# SOLoRa.net
KiCad netlist of a schematic drawn in EAGLE
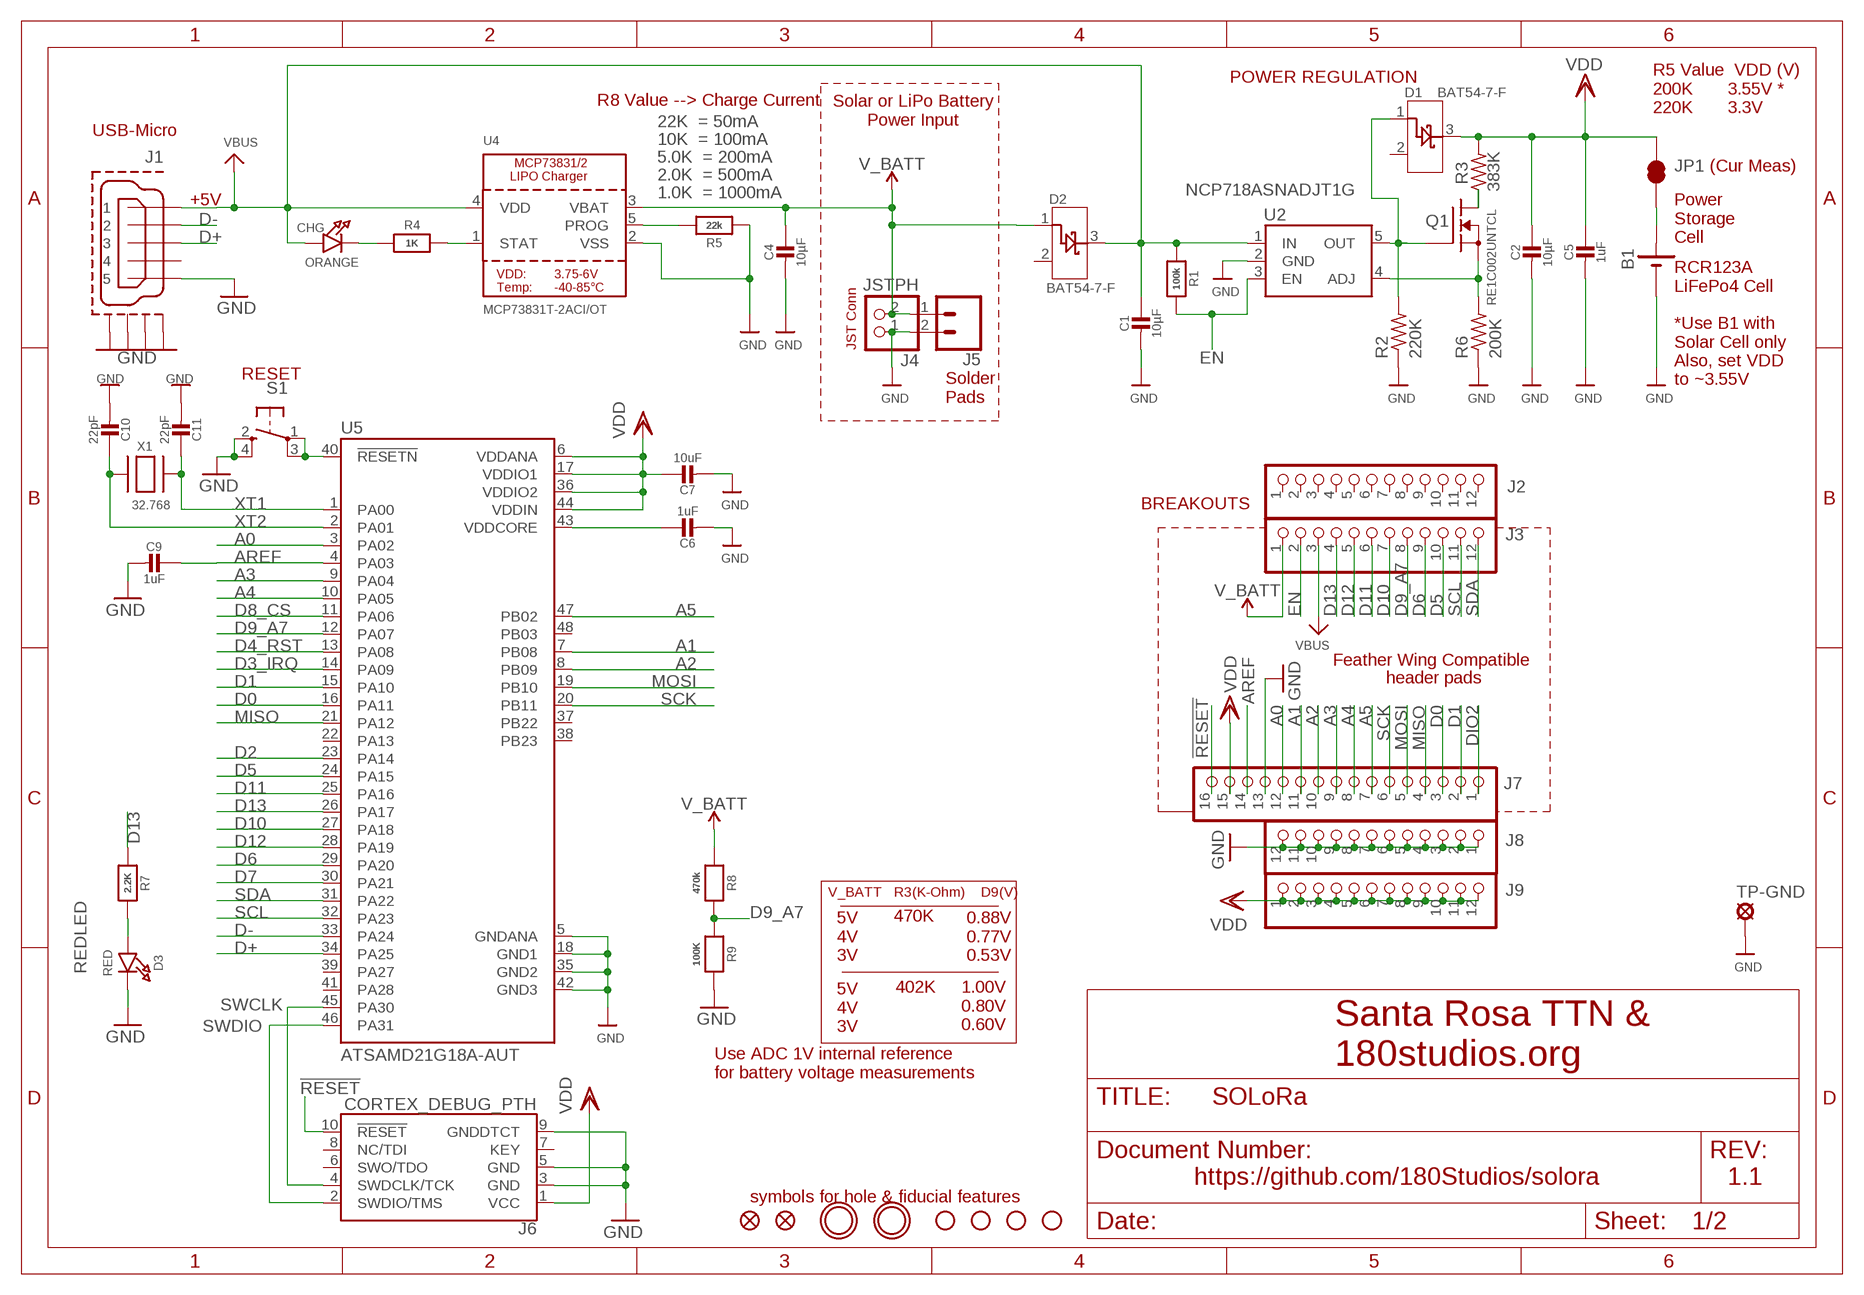
[diagram p0: schematic, sheet 1]
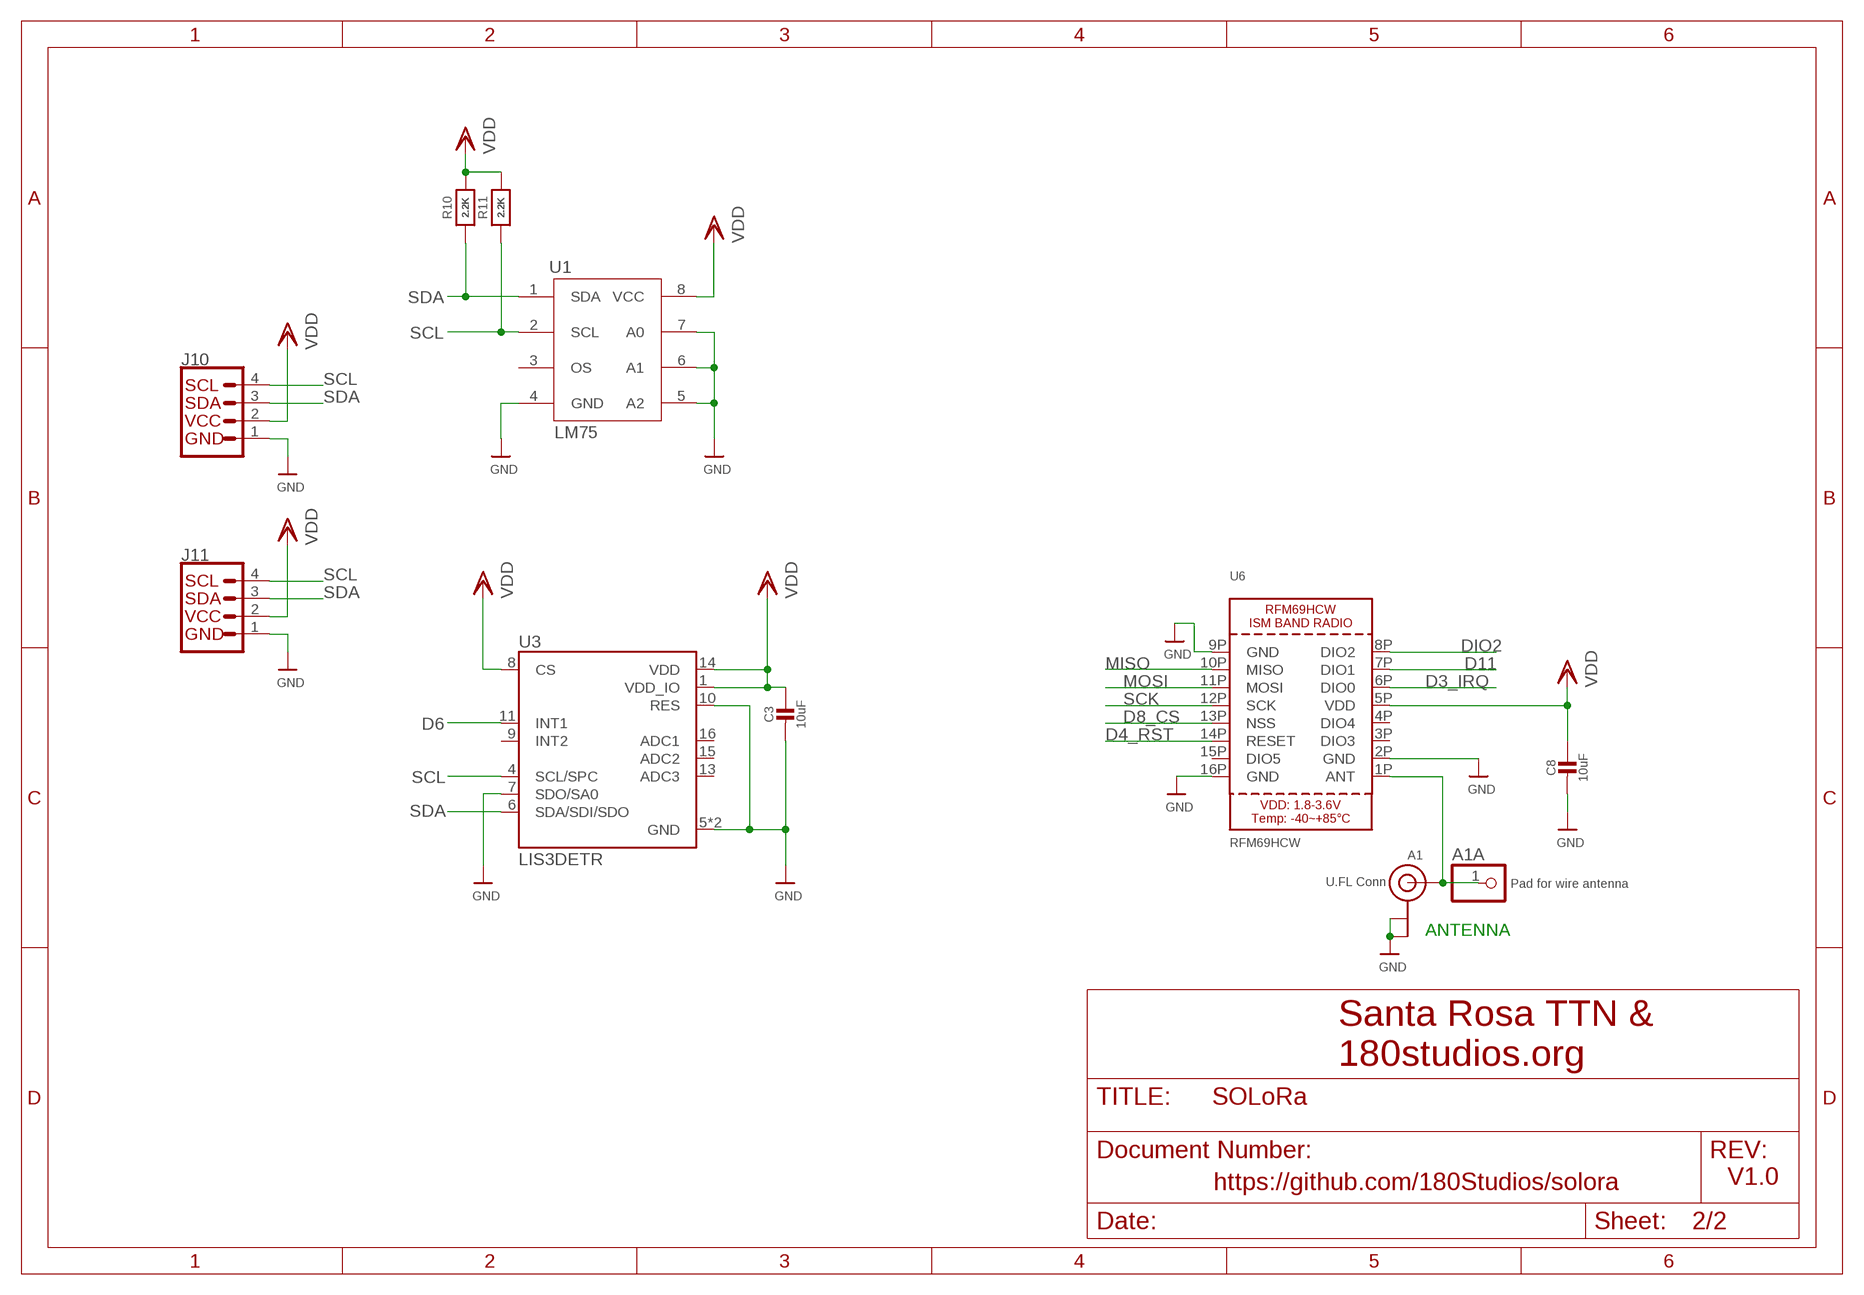
[diagram p1: schematic, sheet 2]

(export (version "E")
  (design (tool "Eeschema 10.0.6"))
  (components
    (comp (ref "$$U$1")
      (value "FIDUCIAL\"\"")
      (footprint "eagle-import:FIDUCIAL_1MM")
      (libsource (lib "eagle-import") (part "FIDUCIAL{dblquote}{dblquote}"))
    )
    (comp (ref "$$U$2")
      (value "MOUNTINGHOLE2.5")
      (footprint "eagle-import:MOUNTINGHOLE_2.5_PLATED")
      (libsource (lib "eagle-import") (part "MOUNTINGHOLE2.5"))
    )
    (comp (ref "$$U$3")
      (value "MOUNTINGHOLE2.5")
      (footprint "eagle-import:MOUNTINGHOLE_2.5_PLATED")
      (libsource (lib "eagle-import") (part "MOUNTINGHOLE2.5"))
    )
    (comp (ref "$$U$4")
      (value "FIDUCIAL\"\"")
      (footprint "eagle-import:FIDUCIAL_1MM")
      (libsource (lib "eagle-import") (part "FIDUCIAL{dblquote}{dblquote}"))
    )
    (comp (ref "B1")
      (value "BH123A")
      (footprint "eagle-import:BH123A")
      (libsource (lib "eagle-import") (part "BH123A"))
    )
    (comp (ref "C1")
      (value "10µF")
      (footprint "eagle-import:0805-NO")
      (libsource (lib "eagle-import") (part "CAP_CERAMIC0805-NOOUTLINE"))
    )
    (comp (ref "C2")
      (value "10µF")
      (footprint "eagle-import:0805-NO")
      (libsource (lib "eagle-import") (part "CAP_CERAMIC0805-NOOUTLINE"))
    )
    (comp (ref "C4")
      (value "10µF")
      (footprint "eagle-import:0805-NO")
      (libsource (lib "eagle-import") (part "CAP_CERAMIC0805-NOOUTLINE"))
    )
    (comp (ref "C5")
      (value "1uF")
      (footprint "eagle-import:0603-NO")
      (libsource (lib "eagle-import") (part "CAP_CERAMIC0603_NO"))
    )
    (comp (ref "C6")
      (value "1uF")
      (footprint "eagle-import:0603-NO")
      (libsource (lib "eagle-import") (part "CAP_CERAMIC0603_NO"))
    )
    (comp (ref "C7")
      (value "10uF")
      (footprint "eagle-import:0805-NO")
      (libsource (lib "eagle-import") (part "CAP_CERAMIC0805-NOOUTLINE"))
    )
    (comp (ref "C9")
      (value "1uF")
      (footprint "eagle-import:0603-NO")
      (libsource (lib "eagle-import") (part "CAP_CERAMIC0603_NO"))
    )
    (comp (ref "C10")
      (value "22pF")
      (footprint "eagle-import:0603-NO")
      (libsource (lib "eagle-import") (part "CAP_CERAMIC0603_NO"))
    )
    (comp (ref "C11")
      (value "22pF")
      (footprint "eagle-import:0603-NO")
      (libsource (lib "eagle-import") (part "CAP_CERAMIC0603_NO"))
    )
    (comp (ref "CHG")
      (value "ORANGE")
      (footprint "eagle-import:CHIPLED_0805_NOOUTLINE")
      (libsource (lib "eagle-import") (part "LED0805_NOOUTLINE"))
    )
    (comp (ref "D1")
      (value "BAT54-7-F")
      (footprint "eagle-import:SOT-23")
      (fields (field (name "MANUFACTURER_PART_NUMBER") "BAT547F"))
      (libsource (lib "eagle-import") (part "BAT54-7-F"))
    )
    (comp (ref "D2")
      (value "BAT54-7-F")
      (footprint "eagle-import:SOT-23")
      (fields (field (name "MANUFACTURER_PART_NUMBER") "BAT547F"))
      (libsource (lib "eagle-import") (part "BAT54-7-F"))
    )
    (comp (ref "D3")
      (value "RED")
      (footprint "eagle-import:CHIPLED_0805_NOOUTLINE")
      (libsource (lib "eagle-import") (part "LED0805_NOOUTLINE"))
    )
    (comp (ref "H1")
      (value "STAND-OFF")
      (footprint "eagle-import:STAND-OFF")
      (libsource (lib "eagle-import") (part "STAND-OFF"))
    )
    (comp (ref "H2")
      (value "STAND-OFF")
      (footprint "eagle-import:STAND-OFF")
      (libsource (lib "eagle-import") (part "STAND-OFF"))
    )
    (comp (ref "H3")
      (value "STAND-OFF")
      (footprint "eagle-import:STAND-OFF")
      (libsource (lib "eagle-import") (part "STAND-OFF"))
    )
    (comp (ref "H4")
      (value "STAND-OFF")
      (footprint "eagle-import:STAND-OFF")
      (libsource (lib "eagle-import") (part "STAND-OFF"))
    )
    (comp (ref "J1")
      (value "CONN_USB-MIRCO_10118194")
      (footprint "eagle-import:10118194_USB")
      (libsource (lib "eagle-import") (part "CONN_USB-MIRCO_10118194"))
    )
    (comp (ref "J2")
      (value "HEADER-1X12")
      (footprint "eagle-import:1X12_ROUND")
      (libsource (lib "eagle-import") (part "HEADER-1X12"))
    )
    (comp (ref "J3")
      (value "HEADER-1X12")
      (footprint "eagle-import:1X12_ROUND")
      (libsource (lib "eagle-import") (part "HEADER-1X12"))
    )
    (comp (ref "J4")
      (value "JSTPH")
      (footprint "eagle-import:JSTPH2")
      (libsource (lib "eagle-import") (part "CON_JST_PH_2PIN"))
    )
    (comp (ref "J5")
      (value "CONN_021X02_NO_SILK")
      (footprint "eagle-import:1X02_NO_SILK")
      (libsource (lib "eagle-import") (part "CONN_021X02_NO_SILK"))
    )
    (comp (ref "J6")
      (value "CORTEX_DEBUG_PTH")
      (footprint "eagle-import:2X5-PTH-1.27MM")
      (libsource (lib "eagle-import") (part "CORTEX_DEBUG_PTH"))
    )
    (comp (ref "J7")
      (value "HEADER-1X16ROUND")
      (footprint "eagle-import:1X16_ROUND")
      (libsource (lib "eagle-import") (part "HEADER-1X16ROUND"))
    )
    (comp (ref "J8")
      (value "HEADER-1X12")
      (footprint "eagle-import:1X12_ROUND")
      (libsource (lib "eagle-import") (part "HEADER-1X12"))
    )
    (comp (ref "J9")
      (value "HEADER-1X12")
      (footprint "eagle-import:1X12_ROUND")
      (libsource (lib "eagle-import") (part "HEADER-1X12"))
    )
    (comp (ref "JP1")
      (value "JUMPER-SMT_2_NC_TRACE_NO-SILK")
      (footprint "eagle-import:SMT-JUMPER_2_NC_TRACE_NO-SILK")
      (libsource (lib "eagle-import") (part "JUMPER-SMT_2_NC_TRACE_NO-SILK"))
    )
    (comp (ref "Q1")
      (value "RE1C002UNTCL")
      (footprint "eagle-import:SOT50P160X85-3N")
      (fields (field (name "RS_PART_NUMBER") "1246784P"))
      (libsource (lib "eagle-import") (part "RE1C002UNTCL"))
    )
    (comp (ref "R1")
      (value "100k")
      (footprint "eagle-import:0603-NO")
      (libsource (lib "eagle-import") (part "RESISTOR_0603_NOOUT"))
    )
    (comp (ref "R2")
      (value "220K")
      (footprint "eagle-import:R0603")
      (libsource (lib "eagle-import") (part "R-US_R0603"))
    )
    (comp (ref "R3")
      (value "383K")
      (footprint "eagle-import:R0603")
      (libsource (lib "eagle-import") (part "R-US_R0603"))
    )
    (comp (ref "R4")
      (value "1K")
      (footprint "eagle-import:0603-NO")
      (libsource (lib "eagle-import") (part "RESISTOR_0603_NOOUT"))
    )
    (comp (ref "R5")
      (value "22k")
      (footprint "eagle-import:0603-NO")
      (libsource (lib "eagle-import") (part "RESISTOR_0603_NOOUT"))
    )
    (comp (ref "R6")
      (value "200K")
      (footprint "eagle-import:R0603")
      (libsource (lib "eagle-import") (part "R-US_R0603"))
    )
    (comp (ref "R7")
      (value "2.2K")
      (footprint "eagle-import:0603-NO")
      (libsource (lib "eagle-import") (part "RESISTOR_0603_NOOUT"))
    )
    (comp (ref "R8")
      (value "470k")
      (footprint "eagle-import:0603-NO")
      (libsource (lib "eagle-import") (part "RESISTOR_0603_NOOUT"))
    )
    (comp (ref "R9")
      (value "100K")
      (footprint "eagle-import:0603-NO")
      (libsource (lib "eagle-import") (part "RESISTOR_0603_NOOUT"))
    )
    (comp (ref "S1")
      (value "SPST_TACT-KMR2")
      (footprint "eagle-import:KMR2")
      (libsource (lib "eagle-import") (part "SPST_TACT-KMR2"))
    )
    (comp (ref "TP-GND")
      (value "SE14")
      (footprint "eagle-import:SE14")
      (libsource (lib "eagle-import") (part "SE14"))
    )
    (comp (ref "U2")
      (value "NCP718ASNADJT1G")
      (footprint "eagle-import:SOT95P280X100-5N")
      (fields (field (name "RS_PART_NUMBER") "1723327"))
      (libsource (lib "eagle-import") (part "NCP718ASNADJT1G"))
    )
    (comp (ref "U4")
      (value "MCP73831T-2ACI/OT")
      (footprint "eagle-import:SOT23-5")
      (libsource (lib "eagle-import") (part "MCP73831/2"))
    )
    (comp (ref "U5")
      (value "ATSAMD21G18A-AUT")
      (footprint "eagle-import:QFP50P900X900X120-48N")
      (fields (field (name "DIGI-KEY_PART_NUMBER") "ATSAMD21G18A-AUTCT-ND") (field (name "MF") "Microchip"))
      (libsource (lib "eagle-import") (part "ATSAMD21G18A-AUT"))
    )
    (comp (ref "X1")
      (value "32.768")
      (footprint "eagle-import:XTAL3215")
      (libsource (lib "eagle-import") (part "XTAL-3.2X1.5"))
    )
    (comp (ref "A1")
      (value "U.FL Conn")
      (footprint "eagle-import:U.FL")
      (libsource (lib "eagle-import") (part "ANTENNA_U.FL"))
    )
    (comp (ref "A1A")
      (value "Pad for wire antenna")
      (footprint "eagle-import:1X01_ROUND")
      (libsource (lib "eagle-import") (part "HEADER-1X1ROUND"))
    )
    (comp (ref "C3")
      (value "10uF")
      (footprint "eagle-import:0805-NO")
      (libsource (lib "eagle-import") (part "CAP_CERAMIC0805-NOOUTLINE"))
    )
    (comp (ref "C8")
      (value "10uF")
      (footprint "eagle-import:0805-NO")
      (libsource (lib "eagle-import") (part "CAP_CERAMIC0805-NOOUTLINE"))
    )
    (comp (ref "J10")
      (value "QWIIC_CONNECTORJS-1MM")
      (footprint "eagle-import:1X04_1MM_RA")
      (libsource (lib "eagle-import") (part "QWIIC_CONNECTORJS-1MM"))
    )
    (comp (ref "J11")
      (value "QWIIC_CONNECTORJS-1MM")
      (footprint "eagle-import:1X04_1MM_RA")
      (libsource (lib "eagle-import") (part "QWIIC_CONNECTORJS-1MM"))
    )
    (comp (ref "R10")
      (value "2.2K")
      (footprint "eagle-import:0603-NO")
      (libsource (lib "eagle-import") (part "RESISTOR_0603_NOOUT"))
    )
    (comp (ref "R11")
      (value "2.2K")
      (footprint "eagle-import:0603-NO")
      (libsource (lib "eagle-import") (part "RESISTOR_0603_NOOUT"))
    )
    (comp (ref "U1")
      (value "LM75")
      (footprint "eagle-import:SO8")
      (libsource (lib "eagle-import") (part "LM75"))
    )
    (comp (ref "U3")
      (value "LIS3DETR")
      (footprint "eagle-import:LGA16R50P5X3_300X300X100N")
      (fields (field (name "DIGI-KEY_PART_NUMBER") "497-16262-1-ND") (field (name "MF") "STMicroelectronics"))
      (libsource (lib "eagle-import") (part "LIS3DETR"))
    )
    (comp (ref "U6")
      (value "RFM69HCW")
      (footprint "eagle-import:RFMHCW_SMT")
      (libsource (lib "eagle-import") (part "RFM69HCW_SMT"))
    )
  )
  (nets
    (net (code "1") (name "A0") (class "Default")
      (node (ref "J7") (pin "12") (pinfunction "12_12") (pintype "passive"))
      (node (ref "U5") (pin "3") (pinfunction "PA02_3") (pintype "bidirectional"))
    )
    (net (code "2") (name "A1") (class "Default")
      (node (ref "J7") (pin "11") (pinfunction "11_11") (pintype "passive"))
      (node (ref "U5") (pin "7") (pinfunction "PB08_7") (pintype "bidirectional"))
    )
    (net (code "3") (name "A2") (class "Default")
      (node (ref "J7") (pin "10") (pinfunction "10_10") (pintype "passive"))
      (node (ref "U5") (pin "8") (pinfunction "PB09_8") (pintype "bidirectional"))
    )
    (net (code "4") (name "A3") (class "Default")
      (node (ref "J7") (pin "9") (pinfunction "9_9") (pintype "passive"))
      (node (ref "U5") (pin "9") (pinfunction "PA04_9") (pintype "bidirectional"))
    )
    (net (code "5") (name "A4") (class "Default")
      (node (ref "J7") (pin "8") (pinfunction "8_8") (pintype "passive"))
      (node (ref "U5") (pin "10") (pinfunction "PA05_10") (pintype "bidirectional"))
    )
    (net (code "6") (name "A5") (class "Default")
      (node (ref "J7") (pin "7") (pinfunction "7_7") (pintype "passive"))
      (node (ref "U5") (pin "47") (pinfunction "PB02_47") (pintype "bidirectional"))
    )
    (net (code "7") (name "AREF") (class "Default")
      (node (ref "C9") (pin "1") (pinfunction "1_1") (pintype "passive"))
      (node (ref "J7") (pin "14") (pinfunction "14_14") (pintype "passive"))
      (node (ref "U5") (pin "4") (pinfunction "PA03_4") (pintype "bidirectional"))
    )
    (net (code "8") (name "D+") (class "Default")
      (node (ref "J1") (pin "3") (pinfunction "3_3") (pintype "input"))
      (node (ref "U5") (pin "34") (pinfunction "PA25_34") (pintype "bidirectional"))
    )
    (net (code "9") (name "D-") (class "Default")
      (node (ref "J1") (pin "2") (pinfunction "2_2") (pintype "input"))
      (node (ref "U5") (pin "33") (pinfunction "PA24_33") (pintype "bidirectional"))
    )
    (net (code "10") (name "D0") (class "Default")
      (node (ref "J7") (pin "3") (pinfunction "3_3") (pintype "passive"))
      (node (ref "U5") (pin "16") (pinfunction "PA11_16") (pintype "bidirectional"))
    )
    (net (code "11") (name "D1") (class "Default")
      (node (ref "J7") (pin "2") (pinfunction "2_2") (pintype "passive"))
      (node (ref "U5") (pin "15") (pinfunction "PA10_15") (pintype "bidirectional"))
    )
    (net (code "12") (name "D2") (class "Default")
      (node (ref "U5") (pin "23") (pinfunction "PA14_23") (pintype "bidirectional"))
    )
    (net (code "13") (name "D3_IRQ") (class "Default")
      (node (ref "U5") (pin "14") (pinfunction "PA09_14") (pintype "bidirectional"))
      (node (ref "U6") (pin "6P") (pinfunction "DIO0_6P") (pintype "bidirectional"))
    )
    (net (code "14") (name "D4_RST") (class "Default")
      (node (ref "U5") (pin "13") (pinfunction "PA08_13") (pintype "bidirectional"))
      (node (ref "U6") (pin "14P") (pinfunction "RESET_14P") (pintype "input"))
    )
    (net (code "15") (name "D5") (class "Default")
      (node (ref "J3") (pin "10") (pinfunction "10_10") (pintype "passive"))
      (node (ref "U5") (pin "24") (pinfunction "PA15_24") (pintype "bidirectional"))
    )
    (net (code "16") (name "D6") (class "Default")
      (node (ref "J3") (pin "9") (pinfunction "9_9") (pintype "passive"))
      (node (ref "U3") (pin "11") (pinfunction "INT1_11") (pintype "input"))
      (node (ref "U5") (pin "29") (pinfunction "PA20_29") (pintype "bidirectional"))
    )
    (net (code "17") (name "D7") (class "Default")
      (node (ref "U5") (pin "30") (pinfunction "PA21_30") (pintype "bidirectional"))
    )
    (net (code "18") (name "D8_CS") (class "Default")
      (node (ref "U5") (pin "11") (pinfunction "PA06_11") (pintype "bidirectional"))
      (node (ref "U6") (pin "13P") (pinfunction "NSS_13P") (pintype "input"))
    )
    (net (code "19") (name "D9_A7") (class "Default")
      (node (ref "J3") (pin "8") (pinfunction "8_8") (pintype "passive"))
      (node (ref "R8") (pin "2") (pinfunction "2_2") (pintype "passive"))
      (node (ref "R9") (pin "1") (pinfunction "1_1") (pintype "passive"))
      (node (ref "U5") (pin "12") (pinfunction "PA07_12") (pintype "bidirectional"))
    )
    (net (code "20") (name "D10") (class "Default")
      (node (ref "J3") (pin "7") (pinfunction "7_7") (pintype "passive"))
      (node (ref "U5") (pin "27") (pinfunction "PA18_27") (pintype "bidirectional"))
    )
    (net (code "21") (name "D11") (class "Default")
      (node (ref "J3") (pin "6") (pinfunction "6_6") (pintype "passive"))
      (node (ref "U5") (pin "25") (pinfunction "PA16_25") (pintype "bidirectional"))
      (node (ref "U6") (pin "7P") (pinfunction "DIO1_7P") (pintype "bidirectional"))
    )
    (net (code "22") (name "D12") (class "Default")
      (node (ref "J3") (pin "5") (pinfunction "5_5") (pintype "passive"))
      (node (ref "U5") (pin "28") (pinfunction "PA19_28") (pintype "bidirectional"))
    )
    (net (code "23") (name "D13") (class "Default")
      (node (ref "J3") (pin "4") (pinfunction "4_4") (pintype "passive"))
      (node (ref "R7") (pin "1") (pinfunction "1_1") (pintype "passive"))
      (node (ref "U5") (pin "26") (pinfunction "PA17_26") (pintype "bidirectional"))
    )
    (net (code "24") (name "DIO2") (class "Default")
      (node (ref "J7") (pin "1") (pinfunction "1_1") (pintype "passive"))
      (node (ref "U6") (pin "8P") (pinfunction "DIO2_8P") (pintype "bidirectional"))
    )
    (net (code "25") (name "EN") (class "Default")
      (node (ref "J3") (pin "2") (pinfunction "2_2") (pintype "passive"))
      (node (ref "R1") (pin "2") (pinfunction "2_2") (pintype "passive"))
      (node (ref "U2") (pin "3") (pinfunction "EN_3") (pintype "bidirectional"))
    )
    (net (code "26") (name "GND") (class "Default")
      (node (ref "A1") (pin "1") (pinfunction "GND_1") (pintype "passive"))
      (node (ref "A1") (pin "2") (pinfunction "GND_2") (pintype "passive"))
      (node (ref "B1") (pin "MINUS") (pinfunction "MINUS_MINUS") (pintype "power_in"))
      (node (ref "C1") (pin "2") (pinfunction "2_2") (pintype "passive"))
      (node (ref "C10") (pin "2") (pinfunction "2_2") (pintype "passive"))
      (node (ref "C11") (pin "2") (pinfunction "2_2") (pintype "passive"))
      (node (ref "C2") (pin "2") (pinfunction "2_2") (pintype "passive"))
      (node (ref "C3") (pin "2") (pinfunction "2_2") (pintype "passive"))
      (node (ref "C4") (pin "2") (pinfunction "2_2") (pintype "passive"))
      (node (ref "C5") (pin "2") (pinfunction "2_2") (pintype "passive"))
      (node (ref "C6") (pin "2") (pinfunction "2_2") (pintype "passive"))
      (node (ref "C7") (pin "2") (pinfunction "2_2") (pintype "passive"))
      (node (ref "C8") (pin "2") (pinfunction "2_2") (pintype "passive"))
      (node (ref "C9") (pin "2") (pinfunction "2_2") (pintype "passive"))
      (node (ref "D3") (pin "C") (pinfunction "C_C") (pintype "passive"))
      (node (ref "J1") (pin "5") (pinfunction "5_5") (pintype "input"))
      (node (ref "J1") (pin "6") (pinfunction "GND1_6") (pintype "bidirectional"))
      (node (ref "J1") (pin "7") (pinfunction "GND2_7") (pintype "bidirectional"))
      (node (ref "J1") (pin "8") (pinfunction "GND3_8") (pintype "bidirectional"))
      (node (ref "J1") (pin "9") (pinfunction "GND4_9") (pintype "bidirectional"))
      (node (ref "J10") (pin "1") (pinfunction "1_1") (pintype "power_in"))
      (node (ref "J11") (pin "1") (pinfunction "1_1") (pintype "power_in"))
      (node (ref "J4") (pin "1") (pinfunction "1_1") (pintype "passive"))
      (node (ref "J5") (pin "2") (pinfunction "2_2") (pintype "passive"))
      (node (ref "J6") (pin "3") (pinfunction "GND_3") (pintype "bidirectional"))
      (node (ref "J6") (pin "5") (pinfunction "GND_5") (pintype "bidirectional"))
      (node (ref "J6") (pin "9") (pinfunction "GNDDTCT_9") (pintype "bidirectional"))
      (node (ref "J7") (pin "13") (pinfunction "13_13") (pintype "passive"))
      (node (ref "J8") (pin "1") (pinfunction "1_1") (pintype "passive"))
      (node (ref "J8") (pin "10") (pinfunction "10_10") (pintype "passive"))
      (node (ref "J8") (pin "11") (pinfunction "11_11") (pintype "passive"))
      (node (ref "J8") (pin "12") (pinfunction "12_12") (pintype "passive"))
      (node (ref "J8") (pin "2") (pinfunction "2_2") (pintype "passive"))
      (node (ref "J8") (pin "3") (pinfunction "3_3") (pintype "passive"))
      (node (ref "J8") (pin "4") (pinfunction "4_4") (pintype "passive"))
      (node (ref "J8") (pin "5") (pinfunction "5_5") (pintype "passive"))
      (node (ref "J8") (pin "6") (pinfunction "6_6") (pintype "passive"))
      (node (ref "J8") (pin "7") (pinfunction "7_7") (pintype "passive"))
      (node (ref "J8") (pin "8") (pinfunction "8_8") (pintype "passive"))
      (node (ref "J8") (pin "9") (pinfunction "9_9") (pintype "passive"))
      (node (ref "R2") (pin "1") (pinfunction "1_1") (pintype "passive"))
      (node (ref "R5") (pin "2") (pinfunction "2_2") (pintype "passive"))
      (node (ref "R6") (pin "1") (pinfunction "1_1") (pintype "passive"))
      (node (ref "R9") (pin "2") (pinfunction "2_2") (pintype "passive"))
      (node (ref "S1") (pin "2") (pinfunction "S_2") (pintype "passive"))
      (node (ref "S1") (pin "4") (pinfunction "S1_4") (pintype "passive"))
      (node (ref "TP-GND") (pin "MP") (pinfunction "MP_MP") (pintype "passive"))
      (node (ref "U1") (pin "4") (pinfunction "GND_4") (pintype "bidirectional"))
      (node (ref "U1") (pin "5") (pinfunction "A2_5") (pintype "bidirectional"))
      (node (ref "U1") (pin "6") (pinfunction "A1_6") (pintype "bidirectional"))
      (node (ref "U1") (pin "7") (pinfunction "A0_7") (pintype "bidirectional"))
      (node (ref "U2") (pin "2") (pinfunction "GND_2") (pintype "bidirectional"))
      (node (ref "U3") (pin "10") (pinfunction "RES_10") (pintype "power_in"))
      (node (ref "U3") (pin "12") (pinfunction "GND_12") (pintype "power_in"))
      (node (ref "U3") (pin "5") (pinfunction "GND_5") (pintype "power_in"))
      (node (ref "U3") (pin "7") (pinfunction "SDO/SA0_7") (pintype "output"))
      (node (ref "U4") (pin "2") (pinfunction "VSS_2") (pintype "power_in"))
      (node (ref "U5") (pin "18") (pinfunction "GND1_18") (pintype "power_in"))
      (node (ref "U5") (pin "35") (pinfunction "GND2_35") (pintype "power_in"))
      (node (ref "U5") (pin "42") (pinfunction "GND3_42") (pintype "power_in"))
      (node (ref "U5") (pin "5") (pinfunction "GNDANA_5") (pintype "power_in"))
      (node (ref "U6") (pin "16P") (pinfunction "GND_16P") (pintype "power_in"))
      (node (ref "U6") (pin "2P") (pinfunction "GND_2P") (pintype "power_in"))
      (node (ref "U6") (pin "9P") (pinfunction "GND_9P") (pintype "power_in"))
    )
    (net (code "27") (name "MISO") (class "Default")
      (node (ref "J7") (pin "4") (pinfunction "4_4") (pintype "passive"))
      (node (ref "U5") (pin "21") (pinfunction "PA12_21") (pintype "bidirectional"))
      (node (ref "U6") (pin "10P") (pinfunction "MISO_10P") (pintype "output"))
    )
    (net (code "28") (name "MOSI") (class "Default")
      (node (ref "J7") (pin "5") (pinfunction "5_5") (pintype "passive"))
      (node (ref "U5") (pin "19") (pinfunction "PB10_19") (pintype "bidirectional"))
      (node (ref "U6") (pin "11P") (pinfunction "MOSI_11P") (pintype "input"))
    )
    (net (code "29") (name "Net-(A1-SIGNAL)") (class "Default")
      (node (ref "A1") (pin "3") (pinfunction "SIGNAL_3") (pintype "passive"))
      (node (ref "A1A") (pin "1") (pinfunction "1_1") (pintype "passive"))
      (node (ref "U6") (pin "1P") (pinfunction "ANT_1P") (pintype "bidirectional"))
    )
    (net (code "30") (name "Net-(B1-PadPLUS)") (class "Default")
      (node (ref "B1") (pin "PLUS") (pinfunction "PLUS_PLUS") (pintype "power_in"))
      (node (ref "JP1") (pin "1") (pinfunction "1_1") (pintype "passive"))
    )
    (net (code "31") (name "Net-(CHG-PadC)") (class "Default")
      (node (ref "CHG") (pin "C") (pinfunction "C_C") (pintype "passive"))
      (node (ref "R4") (pin "1") (pinfunction "1_1") (pintype "passive"))
    )
    (net (code "32") (name "Net-(D1-EPAD1)") (class "Default")
      (node (ref "D1") (pin "1") (pinfunction "EPAD1_1") (pintype "passive"))
      (node (ref "Q1") (pin "1") (pinfunction "G_1") (pintype "passive"))
      (node (ref "R2") (pin "2") (pinfunction "2_2") (pintype "passive"))
      (node (ref "U2") (pin "5") (pinfunction "OUT_5") (pintype "bidirectional"))
    )
    (net (code "33") (name "Net-(Q1-D)") (class "Default")
      (node (ref "Q1") (pin "3") (pinfunction "D_3") (pintype "passive"))
      (node (ref "R3") (pin "1") (pinfunction "1_1") (pintype "passive"))
    )
    (net (code "34") (name "Net-(Q1-S)") (class "Default")
      (node (ref "Q1") (pin "2") (pinfunction "S_2") (pintype "passive"))
      (node (ref "R6") (pin "2") (pinfunction "2_2") (pintype "passive"))
      (node (ref "U2") (pin "4") (pinfunction "ADJ_4") (pintype "bidirectional"))
    )
    (net (code "35") (name "Net-(U4-PROG)") (class "Default")
      (node (ref "R5") (pin "1") (pinfunction "1_1") (pintype "passive"))
      (node (ref "U4") (pin "5") (pinfunction "PROG_5") (pintype "input"))
    )
    (net (code "36") (name "Net-(U4-STAT)") (class "Default")
      (node (ref "R4") (pin "2") (pinfunction "2_2") (pintype "passive"))
      (node (ref "U4") (pin "1") (pinfunction "STAT_1") (pintype "output"))
    )
    (net (code "37") (name "Net-(U5-VDDCORE)") (class "Default")
      (node (ref "C6") (pin "1") (pinfunction "1_1") (pintype "passive"))
      (node (ref "U5") (pin "43") (pinfunction "VDDCORE_43") (pintype "power_in"))
    )
    (net (code "38") (name "REDLED") (class "Default")
      (node (ref "D3") (pin "A") (pinfunction "A_A") (pintype "passive"))
      (node (ref "R7") (pin "2") (pinfunction "2_2") (pintype "passive"))
    )
    (net (code "39") (name "SCK") (class "Default")
      (node (ref "J7") (pin "6") (pinfunction "6_6") (pintype "passive"))
      (node (ref "U5") (pin "20") (pinfunction "PB11_20") (pintype "bidirectional"))
      (node (ref "U6") (pin "12P") (pinfunction "SCK_12P") (pintype "input"))
    )
    (net (code "40") (name "SCL") (class "Default")
      (node (ref "J10") (pin "4") (pinfunction "4_4") (pintype "passive"))
      (node (ref "J11") (pin "4") (pinfunction "4_4") (pintype "passive"))
      (node (ref "J3") (pin "11") (pinfunction "11_11") (pintype "passive"))
      (node (ref "R11") (pin "1") (pinfunction "1_1") (pintype "passive"))
      (node (ref "U1") (pin "2") (pinfunction "SCL_2") (pintype "bidirectional"))
      (node (ref "U3") (pin "4") (pinfunction "SCL/SPC_4") (pintype "input"))
      (node (ref "U5") (pin "32") (pinfunction "PA23_32") (pintype "bidirectional"))
    )
    (net (code "41") (name "SDA") (class "Default")
      (node (ref "J10") (pin "3") (pinfunction "3_3") (pintype "passive"))
      (node (ref "J11") (pin "3") (pinfunction "3_3") (pintype "passive"))
      (node (ref "J3") (pin "12") (pinfunction "12_12") (pintype "passive"))
      (node (ref "R10") (pin "1") (pinfunction "1_1") (pintype "passive"))
      (node (ref "U1") (pin "1") (pinfunction "SDA_1") (pintype "bidirectional"))
      (node (ref "U3") (pin "6") (pinfunction "SDA/SDI/SDO_6") (pintype "bidirectional"))
      (node (ref "U5") (pin "31") (pinfunction "PA22_31") (pintype "bidirectional"))
    )
    (net (code "42") (name "SWCLK") (class "Default")
      (node (ref "J6") (pin "4") (pinfunction "SWDCLK/TCK_4") (pintype "bidirectional"))
      (node (ref "U5") (pin "45") (pinfunction "PA30_45") (pintype "bidirectional"))
    )
    (net (code "43") (name "SWDIO") (class "Default")
      (node (ref "J6") (pin "2") (pinfunction "SWDIO/TMS_2") (pintype "bidirectional"))
      (node (ref "U5") (pin "46") (pinfunction "PA31_46") (pintype "bidirectional"))
    )
    (net (code "44") (name "VBUS") (class "Default")
      (node (ref "C1") (pin "1") (pinfunction "1_1") (pintype "passive"))
      (node (ref "CHG") (pin "A") (pinfunction "A_A") (pintype "passive"))
      (node (ref "D2") (pin "3") (pinfunction "EPAD3_3") (pintype "passive"))
      (node (ref "J1") (pin "1") (pinfunction "1_1") (pintype "input"))
      (node (ref "J3") (pin "3") (pinfunction "3_3") (pintype "passive"))
      (node (ref "R1") (pin "1") (pinfunction "1_1") (pintype "passive"))
      (node (ref "U2") (pin "1") (pinfunction "IN_1") (pintype "bidirectional"))
      (node (ref "U4") (pin "4") (pinfunction "VDD_4") (pintype "power_in"))
    )
    (net (code "45") (name "VDD") (class "Default")
      (node (ref "C2") (pin "1") (pinfunction "1_1") (pintype "passive"))
      (node (ref "C3") (pin "1") (pinfunction "1_1") (pintype "passive"))
      (node (ref "C5") (pin "1") (pinfunction "1_1") (pintype "passive"))
      (node (ref "C7") (pin "1") (pinfunction "1_1") (pintype "passive"))
      (node (ref "C8") (pin "1") (pinfunction "1_1") (pintype "passive"))
      (node (ref "D1") (pin "3") (pinfunction "EPAD3_3") (pintype "passive"))
      (node (ref "J10") (pin "2") (pinfunction "2_2") (pintype "power_in"))
      (node (ref "J11") (pin "2") (pinfunction "2_2") (pintype "power_in"))
      (node (ref "J6") (pin "1") (pinfunction "VCC_1") (pintype "bidirectional"))
      (node (ref "J7") (pin "15") (pinfunction "15_15") (pintype "passive"))
      (node (ref "J9") (pin "1") (pinfunction "1_1") (pintype "passive"))
      (node (ref "J9") (pin "10") (pinfunction "10_10") (pintype "passive"))
      (node (ref "J9") (pin "11") (pinfunction "11_11") (pintype "passive"))
      (node (ref "J9") (pin "12") (pinfunction "12_12") (pintype "passive"))
      (node (ref "J9") (pin "2") (pinfunction "2_2") (pintype "passive"))
      (node (ref "J9") (pin "3") (pinfunction "3_3") (pintype "passive"))
      (node (ref "J9") (pin "4") (pinfunction "4_4") (pintype "passive"))
      (node (ref "J9") (pin "5") (pinfunction "5_5") (pintype "passive"))
      (node (ref "J9") (pin "6") (pinfunction "6_6") (pintype "passive"))
      (node (ref "J9") (pin "7") (pinfunction "7_7") (pintype "passive"))
      (node (ref "J9") (pin "8") (pinfunction "8_8") (pintype "passive"))
      (node (ref "J9") (pin "9") (pinfunction "9_9") (pintype "passive"))
      (node (ref "JP1") (pin "2") (pinfunction "2_2") (pintype "passive"))
      (node (ref "R10") (pin "2") (pinfunction "2_2") (pintype "passive"))
      (node (ref "R11") (pin "2") (pinfunction "2_2") (pintype "passive"))
      (node (ref "R3") (pin "2") (pinfunction "2_2") (pintype "passive"))
      (node (ref "U1") (pin "8") (pinfunction "VCC_8") (pintype "bidirectional"))
      (node (ref "U3") (pin "1") (pinfunction "VDD_IO_1") (pintype "power_in"))
      (node (ref "U3") (pin "14") (pinfunction "VDD_14") (pintype "power_in"))
      (node (ref "U3") (pin "8") (pinfunction "CS_8") (pintype "input"))
      (node (ref "U5") (pin "17") (pinfunction "VDDIO1_17") (pintype "power_in"))
      (node (ref "U5") (pin "36") (pinfunction "VDDIO2_36") (pintype "power_in"))
      (node (ref "U5") (pin "44") (pinfunction "VDDIN_44") (pintype "power_in"))
      (node (ref "U5") (pin "6") (pinfunction "VDDANA_6") (pintype "power_in"))
      (node (ref "U6") (pin "5P") (pinfunction "VDD_5P") (pintype "power_in"))
    )
    (net (code "46") (name "V_BATT") (class "Default")
      (node (ref "C4") (pin "1") (pinfunction "1_1") (pintype "passive"))
      (node (ref "D2") (pin "1") (pinfunction "EPAD1_1") (pintype "passive"))
      (node (ref "J3") (pin "1") (pinfunction "1_1") (pintype "passive"))
      (node (ref "J4") (pin "2") (pinfunction "2_2") (pintype "passive"))
      (node (ref "J5") (pin "1") (pinfunction "1_1") (pintype "passive"))
      (node (ref "R8") (pin "1") (pinfunction "1_1") (pintype "passive"))
      (node (ref "U4") (pin "3") (pinfunction "VBAT_3") (pintype "power_in"))
    )
    (net (code "47") (name "XT1") (class "Default")
      (node (ref "C11") (pin "1") (pinfunction "1_1") (pintype "passive"))
      (node (ref "U5") (pin "1") (pinfunction "PA00_1") (pintype "bidirectional"))
      (node (ref "X1") (pin "P$1") (pinfunction "P$1_P$1") (pintype "bidirectional"))
    )
    (net (code "48") (name "XT2") (class "Default")
      (node (ref "C10") (pin "1") (pinfunction "1_1") (pintype "passive"))
      (node (ref "U5") (pin "2") (pinfunction "PA01_2") (pintype "bidirectional"))
      (node (ref "X1") (pin "P$2") (pinfunction "P$2_P$2") (pintype "bidirectional"))
    )
    (net (code "49") (name "unconnected-(D1-EPAD2-Pad2)") (class "Default")
      (node (ref "D1") (pin "2") (pinfunction "EPAD2_2") (pintype "passive"))
    )
    (net (code "50") (name "unconnected-(D2-EPAD2-Pad2)") (class "Default")
      (node (ref "D2") (pin "2") (pinfunction "EPAD2_2") (pintype "passive"))
    )
    (net (code "51") (name "unconnected-(J1-Pad4)") (class "Default")
      (node (ref "J1") (pin "4") (pinfunction "4_4") (pintype "input"))
    )
    (net (code "52") (name "unconnected-(J2-Pad1)") (class "Default")
      (node (ref "J2") (pin "1") (pinfunction "1_1") (pintype "passive"))
    )
    (net (code "53") (name "unconnected-(J2-Pad2)") (class "Default")
      (node (ref "J2") (pin "2") (pinfunction "2_2") (pintype "passive"))
    )
    (net (code "54") (name "unconnected-(J2-Pad3)") (class "Default")
      (node (ref "J2") (pin "3") (pinfunction "3_3") (pintype "passive"))
    )
    (net (code "55") (name "unconnected-(J2-Pad4)") (class "Default")
      (node (ref "J2") (pin "4") (pinfunction "4_4") (pintype "passive"))
    )
    (net (code "56") (name "unconnected-(J2-Pad5)") (class "Default")
      (node (ref "J2") (pin "5") (pinfunction "5_5") (pintype "passive"))
    )
    (net (code "57") (name "unconnected-(J2-Pad6)") (class "Default")
      (node (ref "J2") (pin "6") (pinfunction "6_6") (pintype "passive"))
    )
    (net (code "58") (name "unconnected-(J2-Pad7)") (class "Default")
      (node (ref "J2") (pin "7") (pinfunction "7_7") (pintype "passive"))
    )
    (net (code "59") (name "unconnected-(J2-Pad8)") (class "Default")
      (node (ref "J2") (pin "8") (pinfunction "8_8") (pintype "passive"))
    )
    (net (code "60") (name "unconnected-(J2-Pad9)") (class "Default")
      (node (ref "J2") (pin "9") (pinfunction "9_9") (pintype "passive"))
    )
    (net (code "61") (name "unconnected-(J2-Pad10)") (class "Default")
      (node (ref "J2") (pin "10") (pinfunction "10_10") (pintype "passive"))
    )
    (net (code "62") (name "unconnected-(J2-Pad11)") (class "Default")
      (node (ref "J2") (pin "11") (pinfunction "11_11") (pintype "passive"))
    )
    (net (code "63") (name "unconnected-(J2-Pad12)") (class "Default")
      (node (ref "J2") (pin "12") (pinfunction "12_12") (pintype "passive"))
    )
    (net (code "64") (name "unconnected-(J6-KEY-Pad7)") (class "Default")
      (node (ref "J6") (pin "7") (pinfunction "KEY_7") (pintype "bidirectional"))
    )
    (net (code "65") (name "unconnected-(J6-NC{slash}TDI-Pad8)") (class "Default")
      (node (ref "J6") (pin "8") (pinfunction "NC/TDI_8") (pintype "bidirectional"))
    )
    (net (code "66") (name "unconnected-(J6-SWO{slash}TDO-Pad6)") (class "Default")
      (node (ref "J6") (pin "6") (pinfunction "SWO/TDO_6") (pintype "bidirectional"))
    )
    (net (code "67") (name "unconnected-(U1-OS-Pad3)") (class "Default")
      (node (ref "U1") (pin "3") (pinfunction "OS_3") (pintype "bidirectional"))
    )
    (net (code "68") (name "unconnected-(U3-ADC1-Pad16)") (class "Default")
      (node (ref "U3") (pin "16") (pinfunction "ADC1_16") (pintype "input"))
    )
    (net (code "69") (name "unconnected-(U3-ADC2-Pad15)") (class "Default")
      (node (ref "U3") (pin "15") (pinfunction "ADC2_15") (pintype "input"))
    )
    (net (code "70") (name "unconnected-(U3-ADC3-Pad13)") (class "Default")
      (node (ref "U3") (pin "13") (pinfunction "ADC3_13") (pintype "input"))
    )
    (net (code "71") (name "unconnected-(U3-INT2-Pad9)") (class "Default")
      (node (ref "U3") (pin "9") (pinfunction "INT2_9") (pintype "input"))
    )
    (net (code "72") (name "unconnected-(U5-PA13-Pad22)") (class "Default")
      (node (ref "U5") (pin "22") (pinfunction "PA13_22") (pintype "bidirectional"))
    )
    (net (code "73") (name "unconnected-(U5-PA27-Pad39)") (class "Default")
      (node (ref "U5") (pin "39") (pinfunction "PA27_39") (pintype "bidirectional"))
    )
    (net (code "74") (name "unconnected-(U5-PA28-Pad41)") (class "Default")
      (node (ref "U5") (pin "41") (pinfunction "PA28_41") (pintype "bidirectional"))
    )
    (net (code "75") (name "unconnected-(U5-PB03-Pad48)") (class "Default")
      (node (ref "U5") (pin "48") (pinfunction "PB03_48") (pintype "bidirectional"))
    )
    (net (code "76") (name "unconnected-(U5-PB22-Pad37)") (class "Default")
      (node (ref "U5") (pin "37") (pinfunction "PB22_37") (pintype "bidirectional"))
    )
    (net (code "77") (name "unconnected-(U5-PB23-Pad38)") (class "Default")
      (node (ref "U5") (pin "38") (pinfunction "PB23_38") (pintype "bidirectional"))
    )
    (net (code "78") (name "unconnected-(U6-DIO3-Pad3P)") (class "Default")
      (node (ref "U6") (pin "3P") (pinfunction "DIO3_3P") (pintype "bidirectional"))
    )
    (net (code "79") (name "unconnected-(U6-DIO4-Pad4P)") (class "Default")
      (node (ref "U6") (pin "4P") (pinfunction "DIO4_4P") (pintype "bidirectional"))
    )
    (net (code "80") (name "unconnected-(U6-DIO5-Pad15P)") (class "Default")
      (node (ref "U6") (pin "15P") (pinfunction "DIO5_15P") (pintype "bidirectional"))
    )
    (net (code "81") (name "~{RESET}") (class "Default")
      (node (ref "J6") (pin "10") (pinfunction "~{RESET}_10") (pintype "bidirectional"))
      (node (ref "J7") (pin "16") (pinfunction "16_16") (pintype "passive"))
      (node (ref "S1") (pin "1") (pinfunction "P_1") (pintype "passive"))
      (node (ref "S1") (pin "3") (pinfunction "P1_3") (pintype "passive"))
      (node (ref "U5") (pin "40") (pinfunction "~{RESETN}_40") (pintype "input"))
    )
  )
)
